# working.net
KiCad netlist of a schematic drawn in EAGLE
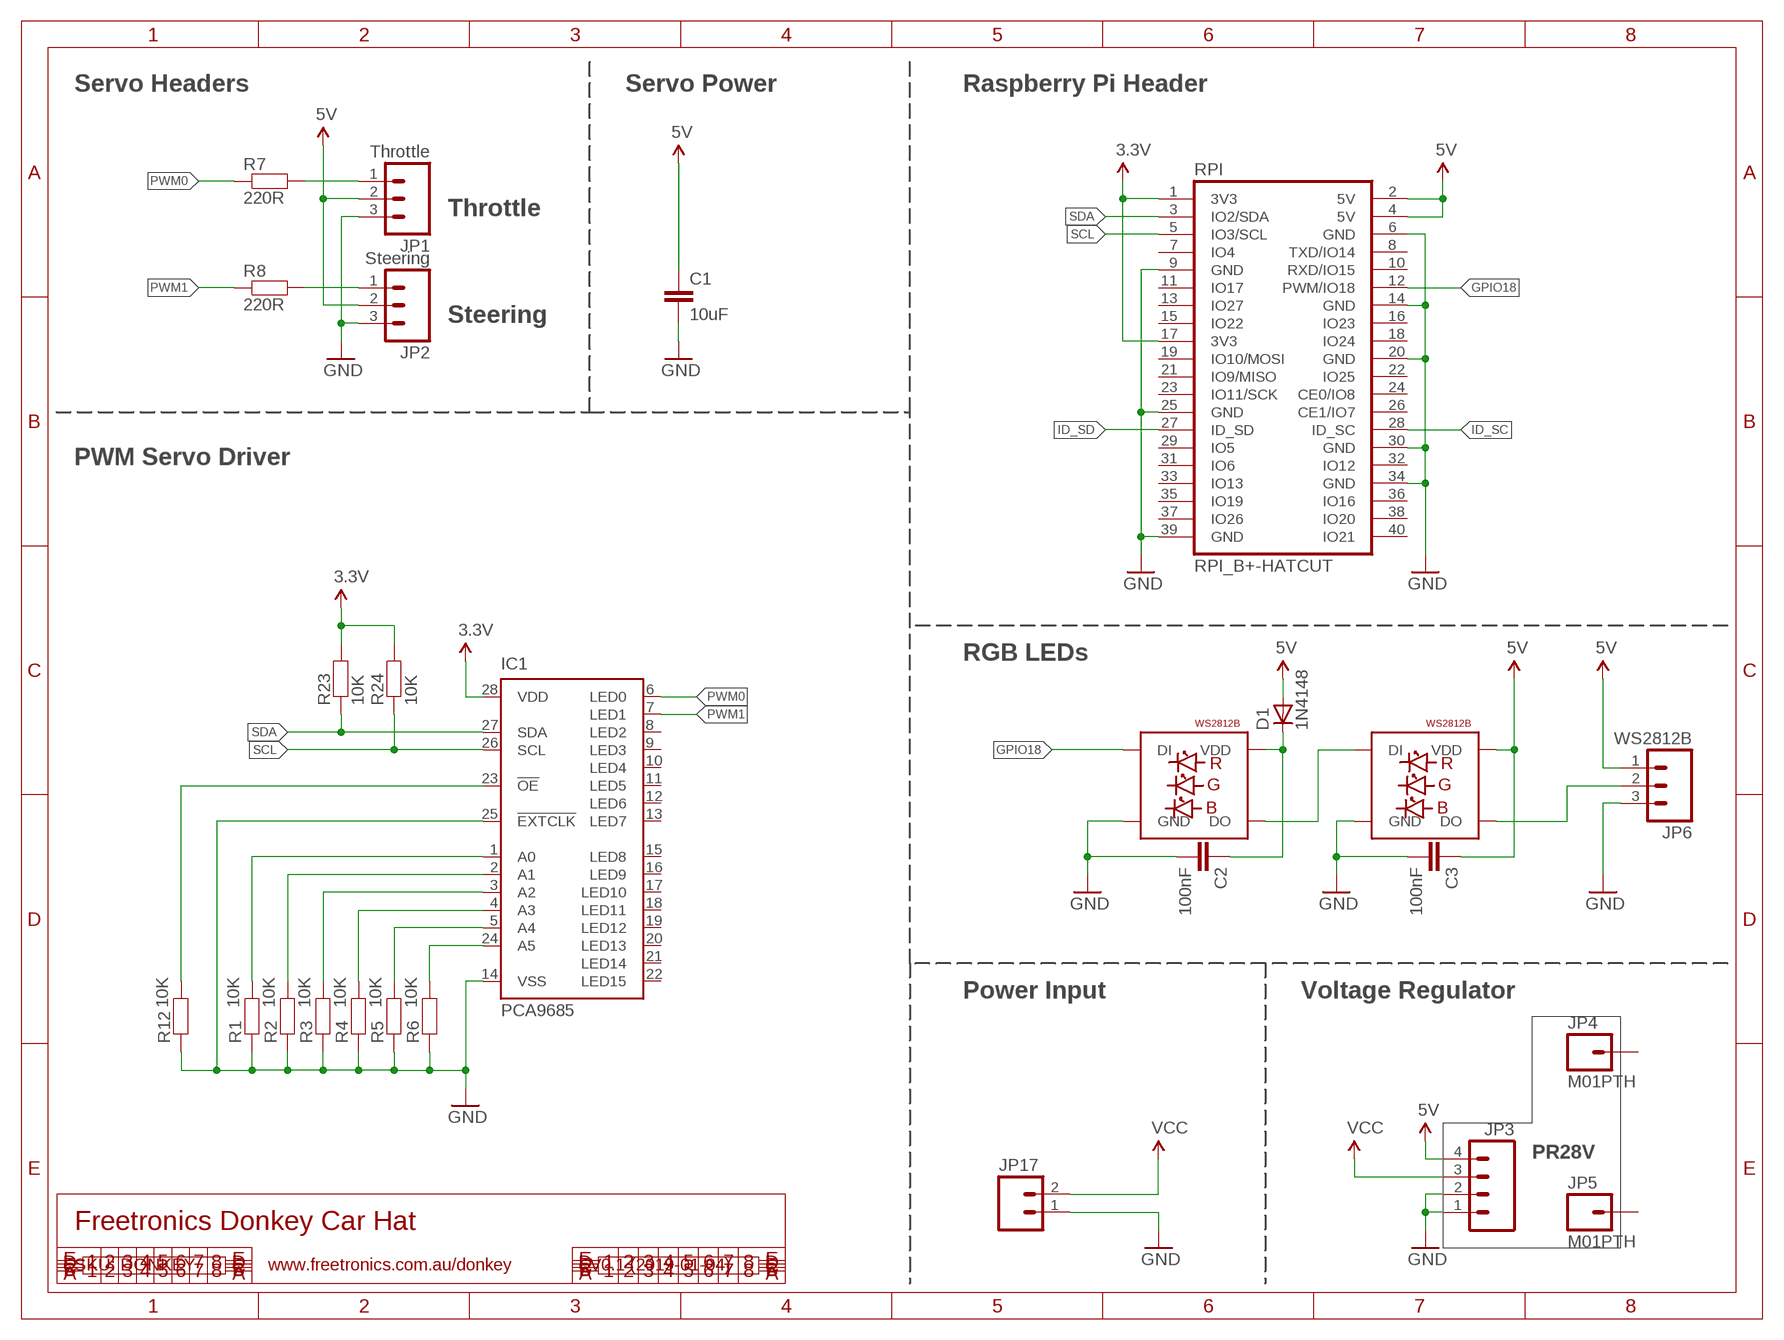
[diagram p0: schematic, sheet 1]

(export (version "E")
  (design (tool "Eeschema 10.0.6"))
  (components
    (comp (ref "C1")
      (value "10uF")
      (footprint "eagle-import:0805")
      (libsource (lib "eagle-import") (part "CAP0805"))
    )
    (comp (ref "C2")
      (value "100nF")
      (footprint "eagle-import:0603")
      (libsource (lib "eagle-import") (part "freetronics-jon_7065448_CAP0603"))
    )
    (comp (ref "C3")
      (value "100nF")
      (footprint "eagle-import:0603")
      (libsource (lib "eagle-import") (part "freetronics-jon_7065448_CAP0603"))
    )
    (comp (ref "D1")
      (value "1N4148")
      (footprint "eagle-import:SOD-323")
      (libsource (lib "eagle-import") (part "DIODESOD"))
    )
    (comp (ref "IC1")
      (value "PCA9685")
      (footprint "eagle-import:TSSOP28")
      (libsource (lib "eagle-import") (part "PCA9685"))
    )
    (comp (ref "JP1")
      (value "Throttle")
      (footprint "eagle-import:1X03")
      (libsource (lib "eagle-import") (part "M03PTH"))
    )
    (comp (ref "JP2")
      (value "Steering")
      (footprint "eagle-import:1X03")
      (libsource (lib "eagle-import") (part "M03PTH"))
    )
    (comp (ref "JP3")
      (value "M04PTH")
      (footprint "eagle-import:1X04")
      (libsource (lib "eagle-import") (part "M04PTH"))
    )
    (comp (ref "JP4")
      (value "M01PTH")
      (footprint "eagle-import:1X01")
      (libsource (lib "eagle-import") (part "M01PTH"))
    )
    (comp (ref "JP5")
      (value "M01PTH")
      (footprint "eagle-import:1X01")
      (libsource (lib "eagle-import") (part "M01PTH"))
    )
    (comp (ref "JP6")
      (value "WS2812B")
      (footprint "eagle-import:1X03")
      (libsource (lib "eagle-import") (part "M03PTH"))
    )
    (comp (ref "JP17")
      (value "M025MM")
      (footprint "eagle-import:SCREWTERMINAL-5MM-2")
      (libsource (lib "eagle-import") (part "M025MM"))
    )
    (comp (ref "LED1")
      (value "WS2812B5050")
      (footprint "eagle-import:WS2812B")
      (libsource (lib "eagle-import") (part "WS2812B5050"))
    )
    (comp (ref "LED2")
      (value "WS2812B5050")
      (footprint "eagle-import:WS2812B")
      (libsource (lib "eagle-import") (part "WS2812B5050"))
    )
    (comp (ref "R1")
      (value "10K")
      (footprint "eagle-import:0603")
      (libsource (lib "eagle-import") (part "RESISTOR0603"))
    )
    (comp (ref "R2")
      (value "10K")
      (footprint "eagle-import:0603")
      (libsource (lib "eagle-import") (part "RESISTOR0603"))
    )
    (comp (ref "R3")
      (value "10K")
      (footprint "eagle-import:0603")
      (libsource (lib "eagle-import") (part "RESISTOR0603"))
    )
    (comp (ref "R4")
      (value "10K")
      (footprint "eagle-import:0603")
      (libsource (lib "eagle-import") (part "RESISTOR0603"))
    )
    (comp (ref "R5")
      (value "10K")
      (footprint "eagle-import:0603")
      (libsource (lib "eagle-import") (part "RESISTOR0603"))
    )
    (comp (ref "R6")
      (value "10K")
      (footprint "eagle-import:0603")
      (libsource (lib "eagle-import") (part "RESISTOR0603"))
    )
    (comp (ref "R7")
      (value "220R")
      (footprint "eagle-import:0603")
      (libsource (lib "eagle-import") (part "RESISTOR0603"))
    )
    (comp (ref "R8")
      (value "220R")
      (footprint "eagle-import:0603")
      (libsource (lib "eagle-import") (part "RESISTOR0603"))
    )
    (comp (ref "R12")
      (value "10K")
      (footprint "eagle-import:0603")
      (libsource (lib "eagle-import") (part "RESISTOR0603"))
    )
    (comp (ref "R23")
      (value "10K")
      (footprint "eagle-import:0603")
      (libsource (lib "eagle-import") (part "RESISTOR0603"))
    )
    (comp (ref "R24")
      (value "10K")
      (footprint "eagle-import:0603")
      (libsource (lib "eagle-import") (part "RESISTOR0603"))
    )
    (comp (ref "RPI")
      (value "RPI_B+-HATCUT")
      (footprint "eagle-import:RPI-B+HAT_CUTOUT")
      (libsource (lib "eagle-import") (part "RPI_B+-HATCUT"))
    )
  )
  (nets
    (net (code "1") (name "3.3V") (class "Default")
      (node (ref "IC1") (pin "28") (pinfunction "VDD_28") (pintype "power_in"))
      (node (ref "R23") (pin "2") (pinfunction "2_2") (pintype "passive"))
      (node (ref "R24") (pin "2") (pinfunction "2_2") (pintype "passive"))
      (node (ref "RPI") (pin "1") (pinfunction "3V3_1") (pintype "passive"))
      (node (ref "RPI") (pin "17") (pinfunction "3V3_17") (pintype "passive"))
    )
    (net (code "2") (name "5V") (class "Default")
      (node (ref "C1") (pin "1") (pinfunction "1_1") (pintype "passive"))
      (node (ref "C3") (pin "1") (pinfunction "1_1") (pintype "passive"))
      (node (ref "D1") (pin "2") (pinfunction "A_2") (pintype "passive"))
      (node (ref "JP1") (pin "2") (pinfunction "2_2") (pintype "passive"))
      (node (ref "JP2") (pin "2") (pinfunction "2_2") (pintype "passive"))
      (node (ref "JP3") (pin "4") (pinfunction "4_4") (pintype "passive"))
      (node (ref "JP6") (pin "1") (pinfunction "1_1") (pintype "passive"))
      (node (ref "LED2") (pin "1-VDD") (pinfunction "VDD_1-VDD") (pintype "power_in"))
      (node (ref "RPI") (pin "2") (pinfunction "5V_2") (pintype "passive"))
      (node (ref "RPI") (pin "4") (pinfunction "5V_4") (pintype "passive"))
    )
    (net (code "3") (name "GND") (class "Default")
      (node (ref "C1") (pin "2") (pinfunction "2_2") (pintype "passive"))
      (node (ref "C2") (pin "2") (pinfunction "2_2") (pintype "passive"))
      (node (ref "C3") (pin "2") (pinfunction "2_2") (pintype "passive"))
      (node (ref "IC1") (pin "14") (pinfunction "VSS_14") (pintype "power_in"))
      (node (ref "IC1") (pin "25") (pinfunction "~{EXTCLK}_25") (pintype "input"))
      (node (ref "JP1") (pin "3") (pinfunction "3_3") (pintype "passive"))
      (node (ref "JP17") (pin "1") (pinfunction "1_1") (pintype "passive"))
      (node (ref "JP2") (pin "3") (pinfunction "3_3") (pintype "passive"))
      (node (ref "JP3") (pin "1") (pinfunction "1_1") (pintype "passive"))
      (node (ref "JP3") (pin "2") (pinfunction "2_2") (pintype "passive"))
      (node (ref "JP6") (pin "3") (pinfunction "3_3") (pintype "passive"))
      (node (ref "LED1") (pin "3-GND") (pinfunction "GND_3-GND") (pintype "power_in"))
      (node (ref "LED2") (pin "3-GND") (pinfunction "GND_3-GND") (pintype "power_in"))
      (node (ref "R1") (pin "1") (pinfunction "1_1") (pintype "passive"))
      (node (ref "R12") (pin "1") (pinfunction "1_1") (pintype "passive"))
      (node (ref "R2") (pin "1") (pinfunction "1_1") (pintype "passive"))
      (node (ref "R3") (pin "1") (pinfunction "1_1") (pintype "passive"))
      (node (ref "R4") (pin "1") (pinfunction "1_1") (pintype "passive"))
      (node (ref "R5") (pin "1") (pinfunction "1_1") (pintype "passive"))
      (node (ref "R6") (pin "1") (pinfunction "1_1") (pintype "passive"))
      (node (ref "RPI") (pin "14") (pinfunction "GND_14") (pintype "passive"))
      (node (ref "RPI") (pin "20") (pinfunction "GND_20") (pintype "passive"))
      (node (ref "RPI") (pin "25") (pinfunction "GND_25") (pintype "passive"))
      (node (ref "RPI") (pin "30") (pinfunction "GND_30") (pintype "bidirectional"))
      (node (ref "RPI") (pin "34") (pinfunction "GND_34") (pintype "bidirectional"))
      (node (ref "RPI") (pin "39") (pinfunction "GND_39") (pintype "bidirectional"))
      (node (ref "RPI") (pin "6") (pinfunction "GND_6") (pintype "passive"))
      (node (ref "RPI") (pin "9") (pinfunction "GND_9") (pintype "passive"))
    )
    (net (code "4") (name "GPIO18") (class "Default")
      (node (ref "LED1") (pin "4-DIN") (pinfunction "DI_4-DIN") (pintype "input"))
      (node (ref "RPI") (pin "12") (pinfunction "PWM/IO18_12") (pintype "passive"))
    )
    (net (code "5") (name "ID_SC") (class "Default")
      (node (ref "RPI") (pin "28") (pinfunction "ID_SC_28") (pintype "bidirectional"))
    )
    (net (code "6") (name "ID_SD") (class "Default")
      (node (ref "RPI") (pin "27") (pinfunction "ID_SD_27") (pintype "bidirectional"))
    )
    (net (code "7") (name "Net-(D1-C)") (class "Default")
      (node (ref "C2") (pin "1") (pinfunction "1_1") (pintype "passive"))
      (node (ref "D1") (pin "1") (pinfunction "C_1") (pintype "passive"))
      (node (ref "LED1") (pin "1-VDD") (pinfunction "VDD_1-VDD") (pintype "power_in"))
    )
    (net (code "8") (name "Net-(IC1-A0)") (class "Default")
      (node (ref "IC1") (pin "1") (pinfunction "A0_1") (pintype "input"))
      (node (ref "R1") (pin "2") (pinfunction "2_2") (pintype "passive"))
    )
    (net (code "9") (name "Net-(IC1-A1)") (class "Default")
      (node (ref "IC1") (pin "2") (pinfunction "A1_2") (pintype "input"))
      (node (ref "R2") (pin "2") (pinfunction "2_2") (pintype "passive"))
    )
    (net (code "10") (name "Net-(IC1-A2)") (class "Default")
      (node (ref "IC1") (pin "3") (pinfunction "A2_3") (pintype "input"))
      (node (ref "R3") (pin "2") (pinfunction "2_2") (pintype "passive"))
    )
    (net (code "11") (name "Net-(IC1-A3)") (class "Default")
      (node (ref "IC1") (pin "4") (pinfunction "A3_4") (pintype "output"))
      (node (ref "R4") (pin "2") (pinfunction "2_2") (pintype "passive"))
    )
    (net (code "12") (name "Net-(IC1-A4)") (class "Default")
      (node (ref "IC1") (pin "5") (pinfunction "A4_5") (pintype "input"))
      (node (ref "R5") (pin "2") (pinfunction "2_2") (pintype "passive"))
    )
    (net (code "13") (name "Net-(IC1-A5)") (class "Default")
      (node (ref "IC1") (pin "24") (pinfunction "A5_24") (pintype "input"))
      (node (ref "R6") (pin "2") (pinfunction "2_2") (pintype "passive"))
    )
    (net (code "14") (name "Net-(IC1-~{OE})") (class "Default")
      (node (ref "IC1") (pin "23") (pinfunction "~{OE}_23") (pintype "input"))
      (node (ref "R12") (pin "2") (pinfunction "2_2") (pintype "passive"))
    )
    (net (code "15") (name "Net-(JP1-Pad1)") (class "Default")
      (node (ref "JP1") (pin "1") (pinfunction "1_1") (pintype "passive"))
      (node (ref "R7") (pin "2") (pinfunction "2_2") (pintype "passive"))
    )
    (net (code "16") (name "Net-(JP2-Pad1)") (class "Default")
      (node (ref "JP2") (pin "1") (pinfunction "1_1") (pintype "passive"))
      (node (ref "R8") (pin "2") (pinfunction "2_2") (pintype "passive"))
    )
    (net (code "17") (name "Net-(LED1-DO)") (class "Default")
      (node (ref "LED1") (pin "2-DOUT") (pinfunction "DO_2-DOUT") (pintype "output"))
      (node (ref "LED2") (pin "4-DIN") (pinfunction "DI_4-DIN") (pintype "input"))
    )
    (net (code "18") (name "Net-(LED2-DO)") (class "Default")
      (node (ref "JP6") (pin "2") (pinfunction "2_2") (pintype "passive"))
      (node (ref "LED2") (pin "2-DOUT") (pinfunction "DO_2-DOUT") (pintype "output"))
    )
    (net (code "19") (name "PWM0") (class "Default")
      (node (ref "IC1") (pin "6") (pinfunction "LED0_6") (pintype "bidirectional"))
      (node (ref "R7") (pin "1") (pinfunction "1_1") (pintype "passive"))
    )
    (net (code "20") (name "PWM1") (class "Default")
      (node (ref "IC1") (pin "7") (pinfunction "LED1_7") (pintype "bidirectional"))
      (node (ref "R8") (pin "1") (pinfunction "1_1") (pintype "passive"))
    )
    (net (code "21") (name "SCL") (class "Default")
      (node (ref "IC1") (pin "26") (pinfunction "SCL_26") (pintype "output"))
      (node (ref "R24") (pin "1") (pinfunction "1_1") (pintype "passive"))
      (node (ref "RPI") (pin "5") (pinfunction "IO3/SCL_5") (pintype "passive"))
    )
    (net (code "22") (name "SDA") (class "Default")
      (node (ref "IC1") (pin "27") (pinfunction "SDA_27") (pintype "output"))
      (node (ref "R23") (pin "1") (pinfunction "1_1") (pintype "passive"))
      (node (ref "RPI") (pin "3") (pinfunction "IO2/SDA_3") (pintype "passive"))
    )
    (net (code "23") (name "VCC") (class "Default")
      (node (ref "JP17") (pin "2") (pinfunction "2_2") (pintype "passive"))
      (node (ref "JP3") (pin "3") (pinfunction "3_3") (pintype "passive"))
    )
    (net (code "24") (name "unconnected-(IC1-LED2-Pad8)") (class "Default")
      (node (ref "IC1") (pin "8") (pinfunction "LED2_8") (pintype "bidirectional"))
    )
    (net (code "25") (name "unconnected-(IC1-LED3-Pad9)") (class "Default")
      (node (ref "IC1") (pin "9") (pinfunction "LED3_9") (pintype "bidirectional"))
    )
    (net (code "26") (name "unconnected-(IC1-LED4-Pad10)") (class "Default")
      (node (ref "IC1") (pin "10") (pinfunction "LED4_10") (pintype "bidirectional"))
    )
    (net (code "27") (name "unconnected-(IC1-LED5-Pad11)") (class "Default")
      (node (ref "IC1") (pin "11") (pinfunction "LED5_11") (pintype "bidirectional"))
    )
    (net (code "28") (name "unconnected-(IC1-LED6-Pad12)") (class "Default")
      (node (ref "IC1") (pin "12") (pinfunction "LED6_12") (pintype "bidirectional"))
    )
    (net (code "29") (name "unconnected-(IC1-LED7-Pad13)") (class "Default")
      (node (ref "IC1") (pin "13") (pinfunction "LED7_13") (pintype "bidirectional"))
    )
    (net (code "30") (name "unconnected-(IC1-LED8-Pad15)") (class "Default")
      (node (ref "IC1") (pin "15") (pinfunction "LED8_15") (pintype "bidirectional"))
    )
    (net (code "31") (name "unconnected-(IC1-LED9-Pad16)") (class "Default")
      (node (ref "IC1") (pin "16") (pinfunction "LED9_16") (pintype "bidirectional"))
    )
    (net (code "32") (name "unconnected-(IC1-LED10-Pad17)") (class "Default")
      (node (ref "IC1") (pin "17") (pinfunction "LED10_17") (pintype "bidirectional"))
    )
    (net (code "33") (name "unconnected-(IC1-LED11-Pad18)") (class "Default")
      (node (ref "IC1") (pin "18") (pinfunction "LED11_18") (pintype "bidirectional"))
    )
    (net (code "34") (name "unconnected-(IC1-LED12-Pad19)") (class "Default")
      (node (ref "IC1") (pin "19") (pinfunction "LED12_19") (pintype "bidirectional"))
    )
    (net (code "35") (name "unconnected-(IC1-LED13-Pad20)") (class "Default")
      (node (ref "IC1") (pin "20") (pinfunction "LED13_20") (pintype "bidirectional"))
    )
    (net (code "36") (name "unconnected-(IC1-LED14-Pad21)") (class "Default")
      (node (ref "IC1") (pin "21") (pinfunction "LED14_21") (pintype "bidirectional"))
    )
    (net (code "37") (name "unconnected-(IC1-LED15-Pad22)") (class "Default")
      (node (ref "IC1") (pin "22") (pinfunction "LED15_22") (pintype "bidirectional"))
    )
    (net (code "38") (name "unconnected-(JP4-Pad1)") (class "Default")
      (node (ref "JP4") (pin "1") (pinfunction "1_1") (pintype "passive"))
    )
    (net (code "39") (name "unconnected-(JP5-Pad1)") (class "Default")
      (node (ref "JP5") (pin "1") (pinfunction "1_1") (pintype "passive"))
    )
    (net (code "40") (name "unconnected-(RPI-CE0{slash}IO8-Pad24)") (class "Default")
      (node (ref "RPI") (pin "24") (pinfunction "CE0/IO8_24") (pintype "passive"))
    )
    (net (code "41") (name "unconnected-(RPI-CE1{slash}IO7-Pad26)") (class "Default")
      (node (ref "RPI") (pin "26") (pinfunction "CE1/IO7_26") (pintype "passive"))
    )
    (net (code "42") (name "unconnected-(RPI-IO4-Pad7)") (class "Default")
      (node (ref "RPI") (pin "7") (pinfunction "IO4_7") (pintype "passive"))
    )
    (net (code "43") (name "unconnected-(RPI-IO5-Pad29)") (class "Default")
      (node (ref "RPI") (pin "29") (pinfunction "IO5_29") (pintype "bidirectional"))
    )
    (net (code "44") (name "unconnected-(RPI-IO6-Pad31)") (class "Default")
      (node (ref "RPI") (pin "31") (pinfunction "IO6_31") (pintype "bidirectional"))
    )
    (net (code "45") (name "unconnected-(RPI-IO9{slash}MISO-Pad21)") (class "Default")
      (node (ref "RPI") (pin "21") (pinfunction "IO9/MISO_21") (pintype "passive"))
    )
    (net (code "46") (name "unconnected-(RPI-IO10{slash}MOSI-Pad19)") (class "Default")
      (node (ref "RPI") (pin "19") (pinfunction "IO10/MOSI_19") (pintype "passive"))
    )
    (net (code "47") (name "unconnected-(RPI-IO11{slash}SCK-Pad23)") (class "Default")
      (node (ref "RPI") (pin "23") (pinfunction "IO11/SCK_23") (pintype "passive"))
    )
    (net (code "48") (name "unconnected-(RPI-IO12-Pad32)") (class "Default")
      (node (ref "RPI") (pin "32") (pinfunction "IO12_32") (pintype "bidirectional"))
    )
    (net (code "49") (name "unconnected-(RPI-IO13-Pad33)") (class "Default")
      (node (ref "RPI") (pin "33") (pinfunction "IO13_33") (pintype "bidirectional"))
    )
    (net (code "50") (name "unconnected-(RPI-IO16-Pad36)") (class "Default")
      (node (ref "RPI") (pin "36") (pinfunction "IO16_36") (pintype "bidirectional"))
    )
    (net (code "51") (name "unconnected-(RPI-IO17-Pad11)") (class "Default")
      (node (ref "RPI") (pin "11") (pinfunction "IO17_11") (pintype "passive"))
    )
    (net (code "52") (name "unconnected-(RPI-IO19-Pad35)") (class "Default")
      (node (ref "RPI") (pin "35") (pinfunction "IO19_35") (pintype "bidirectional"))
    )
    (net (code "53") (name "unconnected-(RPI-IO20-Pad38)") (class "Default")
      (node (ref "RPI") (pin "38") (pinfunction "IO20_38") (pintype "bidirectional"))
    )
    (net (code "54") (name "unconnected-(RPI-IO21-Pad40)") (class "Default")
      (node (ref "RPI") (pin "40") (pinfunction "IO21_40") (pintype "bidirectional"))
    )
    (net (code "55") (name "unconnected-(RPI-IO22-Pad15)") (class "Default")
      (node (ref "RPI") (pin "15") (pinfunction "IO22_15") (pintype "passive"))
    )
    (net (code "56") (name "unconnected-(RPI-IO23-Pad16)") (class "Default")
      (node (ref "RPI") (pin "16") (pinfunction "IO23_16") (pintype "passive"))
    )
    (net (code "57") (name "unconnected-(RPI-IO24-Pad18)") (class "Default")
      (node (ref "RPI") (pin "18") (pinfunction "IO24_18") (pintype "passive"))
    )
    (net (code "58") (name "unconnected-(RPI-IO25-Pad22)") (class "Default")
      (node (ref "RPI") (pin "22") (pinfunction "IO25_22") (pintype "passive"))
    )
    (net (code "59") (name "unconnected-(RPI-IO26-Pad37)") (class "Default")
      (node (ref "RPI") (pin "37") (pinfunction "IO26_37") (pintype "bidirectional"))
    )
    (net (code "60") (name "unconnected-(RPI-IO27-Pad13)") (class "Default")
      (node (ref "RPI") (pin "13") (pinfunction "IO27_13") (pintype "passive"))
    )
    (net (code "61") (name "unconnected-(RPI-RXD{slash}IO15-Pad10)") (class "Default")
      (node (ref "RPI") (pin "10") (pinfunction "RXD/IO15_10") (pintype "passive"))
    )
    (net (code "62") (name "unconnected-(RPI-TXD{slash}IO14-Pad8)") (class "Default")
      (node (ref "RPI") (pin "8") (pinfunction "TXD/IO14_8") (pintype "passive"))
    )
  )
)
